# pierce-test-board-2.net
KiCad netlist of a schematic drawn in EAGLE
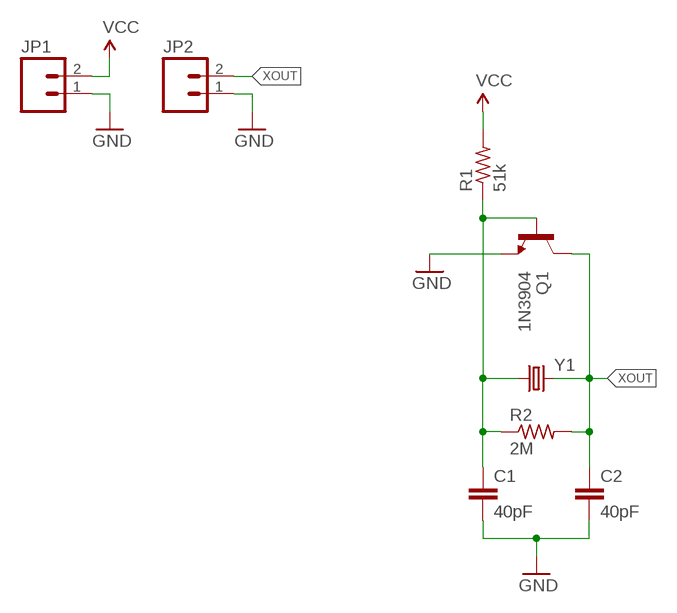
[diagram p0: schematic, sheet 1]

(export (version "E")
  (design (tool "Eeschema 10.0.6"))
  (components
    (comp (ref "C1")
      (value "40pF")
      (footprint "eagle-import:C025-024X044")
      (libsource (lib "eagle-import") (part "CAPACITOR-CERAMIC025-024X044"))
    )
    (comp (ref "C2")
      (value "40pF")
      (footprint "eagle-import:C025-024X044")
      (libsource (lib "eagle-import") (part "CAPACITOR-CERAMIC025-024X044"))
    )
    (comp (ref "JP1")
      (value "M02PTH")
      (footprint "eagle-import:1X02")
      (libsource (lib "eagle-import") (part "M02PTH"))
    )
    (comp (ref "JP2")
      (value "M02PTH")
      (footprint "eagle-import:1X02")
      (libsource (lib "eagle-import") (part "M02PTH"))
    )
    (comp (ref "Q1")
      (value "1N3904")
      (footprint "eagle-import:TO-92-AMMO")
      (libsource (lib "eagle-import") (part "TRANSISTOR_NPNTO-92-AMMO-EBC"))
    )
    (comp (ref "R1")
      (value "51k")
      (footprint "eagle-import:RESISTOR-AXIAL-PTH-7.68MM")
      (libsource (lib "eagle-import") (part "RESISTORAXIAL-PTH-7.68MM"))
    )
    (comp (ref "R2")
      (value "2M")
      (footprint "eagle-import:RESISTOR-AXIAL-PTH-7.68MM")
      (libsource (lib "eagle-import") (part "RESISTORAXIAL-PTH-7.68MM"))
    )
    (comp (ref "Y1")
      (value "CRYSTALHC49UV")
      (footprint "eagle-import:HC49U-V")
      (libsource (lib "eagle-import") (part "CRYSTALHC49UV"))
    )
  )
  (nets
    (net (code "1") (name "GND") (class "Default")
      (node (ref "C1") (pin "2") (pinfunction "2_2") (pintype "passive"))
      (node (ref "C2") (pin "2") (pinfunction "2_2") (pintype "passive"))
      (node (ref "JP1") (pin "1") (pinfunction "1_1") (pintype "passive"))
      (node (ref "JP2") (pin "1") (pinfunction "1_1") (pintype "passive"))
      (node (ref "Q1") (pin "1") (pinfunction "E_1") (pintype "passive"))
    )
    (net (code "2") (name "Net-(Q1-B)") (class "Default")
      (node (ref "C1") (pin "1") (pinfunction "1_1") (pintype "passive"))
      (node (ref "Q1") (pin "2") (pinfunction "B_2") (pintype "passive"))
      (node (ref "R1") (pin "P$1") (pinfunction "1_P$1") (pintype "passive"))
      (node (ref "R2") (pin "P$1") (pinfunction "1_P$1") (pintype "passive"))
      (node (ref "Y1") (pin "1") (pinfunction "1_1") (pintype "passive"))
    )
    (net (code "3") (name "VCC") (class "Default")
      (node (ref "JP1") (pin "2") (pinfunction "2_2") (pintype "passive"))
      (node (ref "R1") (pin "P$2") (pinfunction "2_P$2") (pintype "passive"))
    )
    (net (code "4") (name "XOUT") (class "Default")
      (node (ref "C2") (pin "1") (pinfunction "1_1") (pintype "passive"))
      (node (ref "JP2") (pin "2") (pinfunction "2_2") (pintype "passive"))
      (node (ref "Q1") (pin "3") (pinfunction "C_3") (pintype "passive"))
      (node (ref "R2") (pin "P$2") (pinfunction "2_P$2") (pintype "passive"))
      (node (ref "Y1") (pin "2") (pinfunction "2_2") (pintype "passive"))
    )
  )
)
